# SCH_SrProj_v1_1.net
KiCad netlist of a schematic drawn in EasyEDA
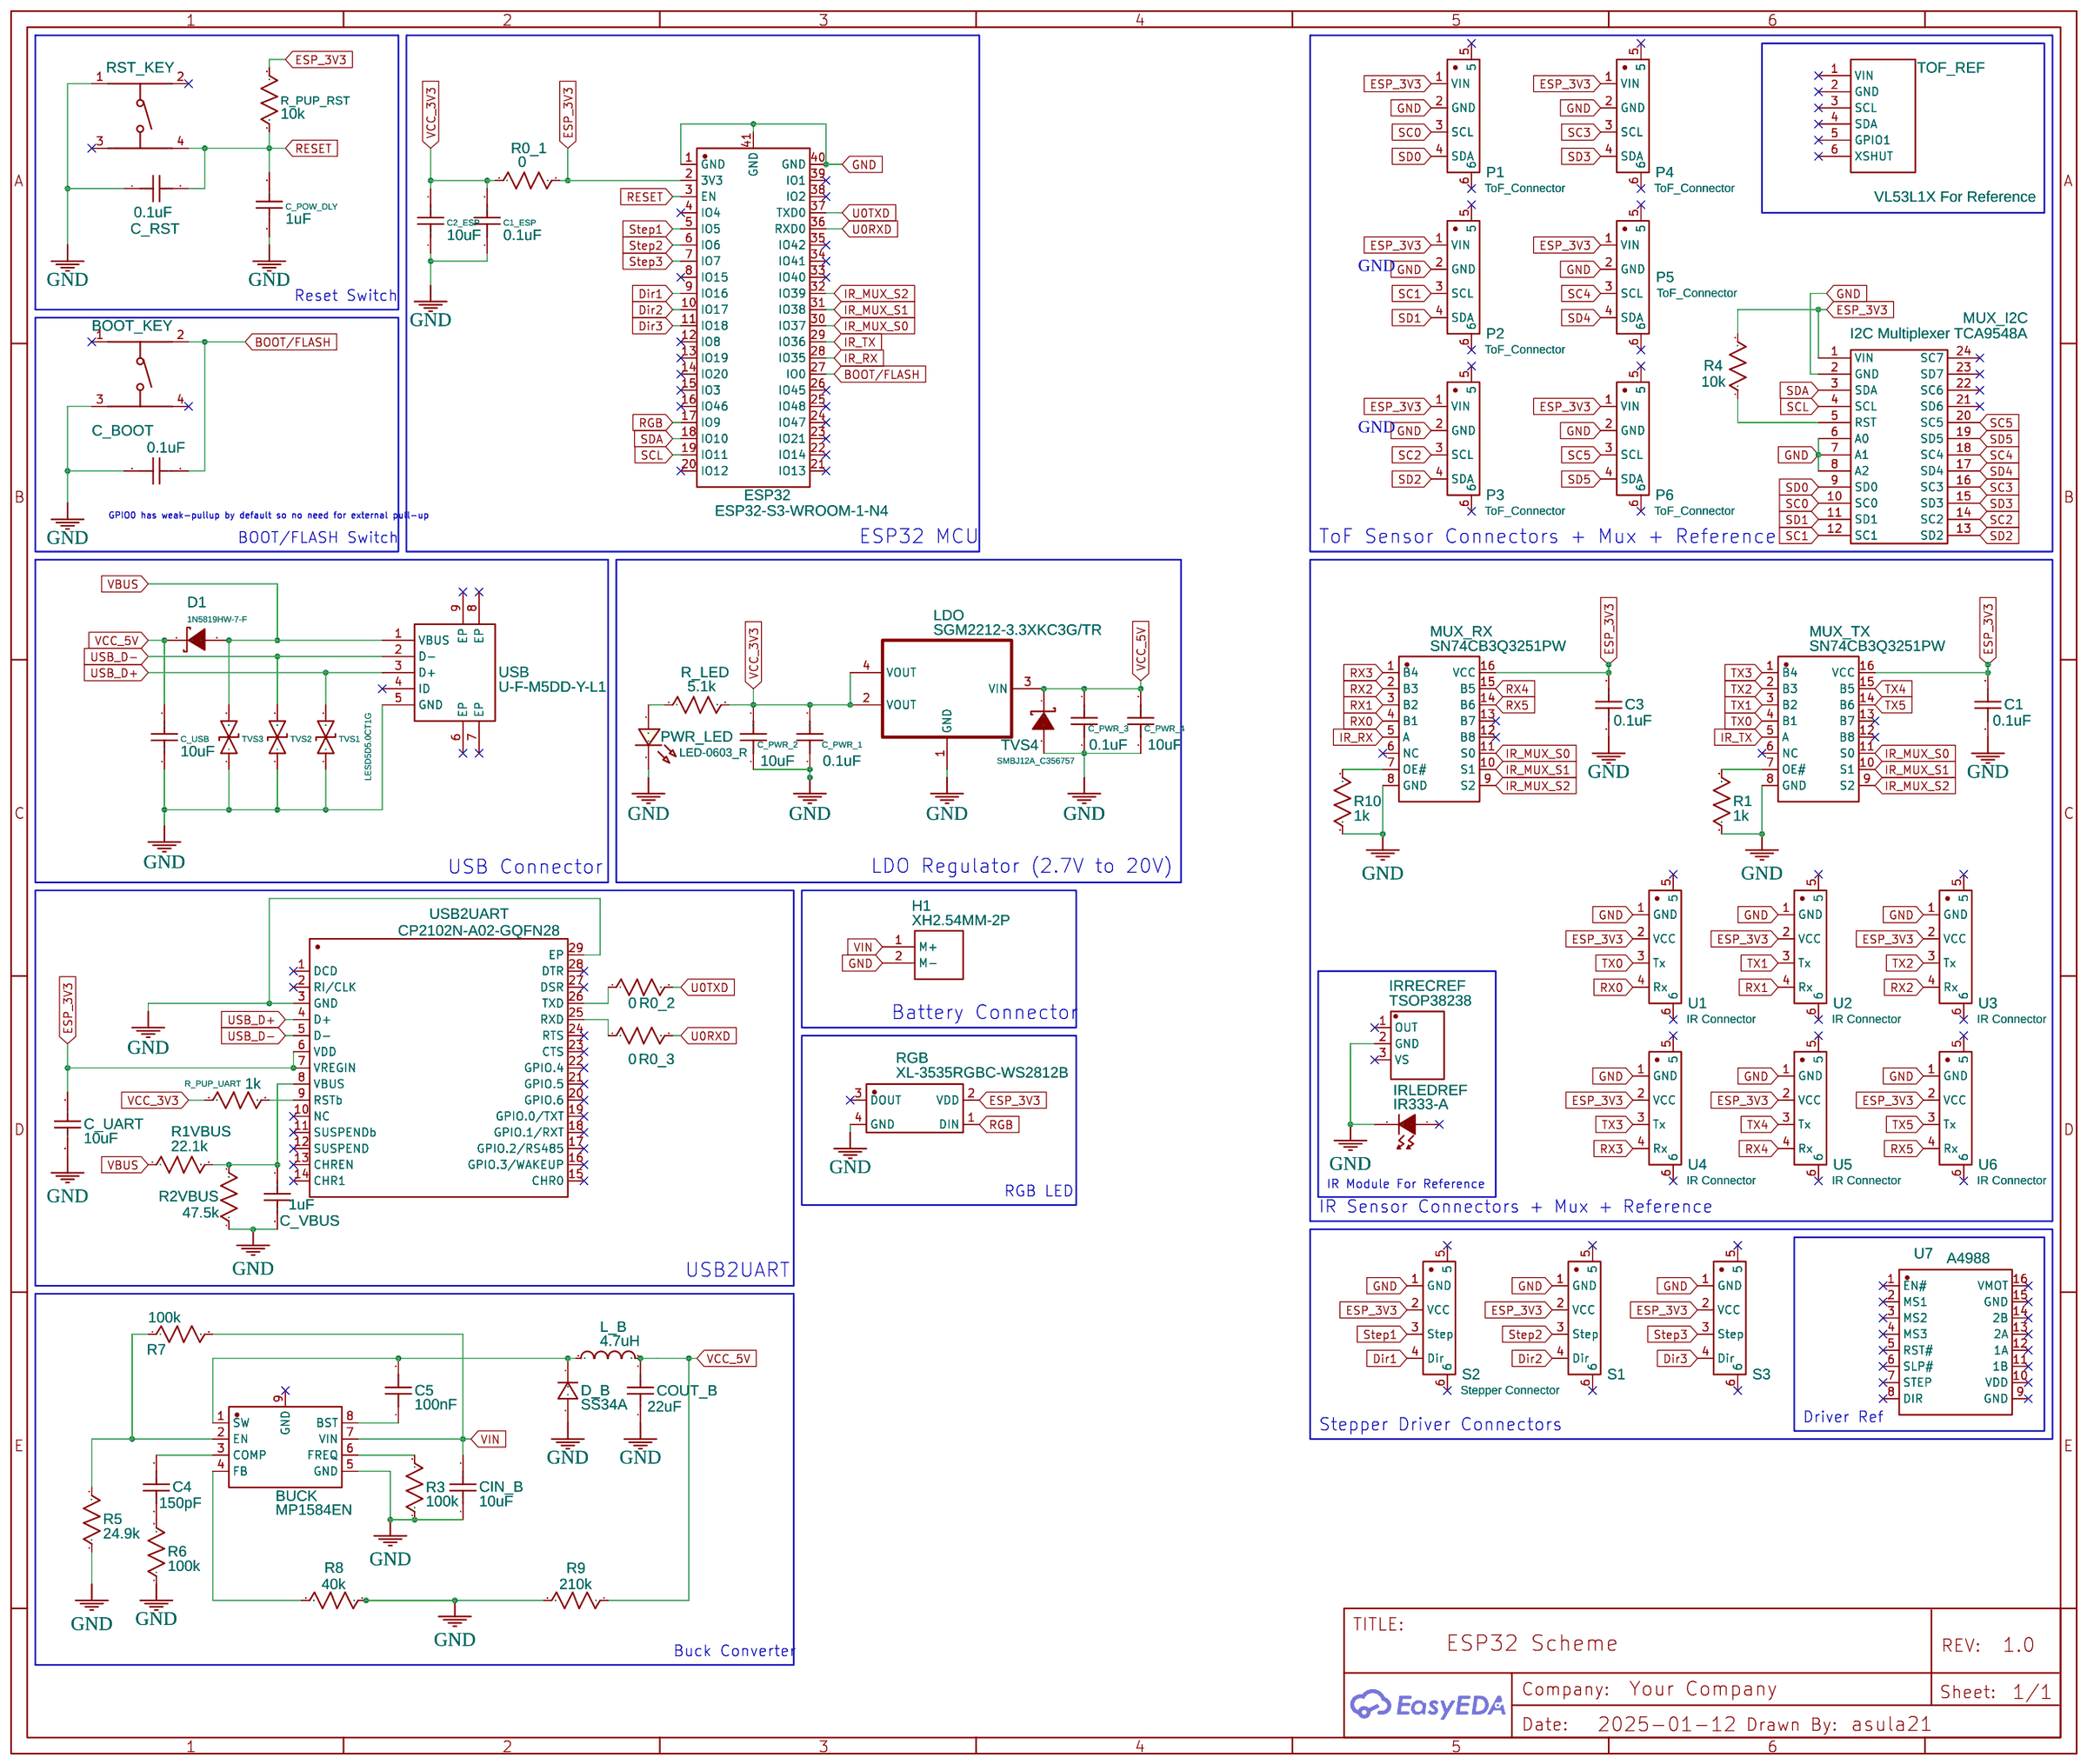
[diagram p0: schematic sheet]

(export (version "E")
  (design (tool "Eeschema 10.0.6"))
  (components
    (comp (ref "BOOT_KEY")
      (value "RSTBTN")
      (fields (field (name "Manufacturer Part") "BUTTON1"))
      (libsource (lib "") (part "BUTTON1_1"))
    )
    (comp (ref "BUCK") (value "MP1584EN") (libsource (lib "") (part "MP1584EN")))
    (comp (ref "C1") (value "0.1uF") (libsource (lib "") (part "C_0603_US_5")))
    (comp (ref "C1_ESP") (value "0.1uF") (libsource (lib "") (part "C_0603_US_10")))
    (comp (ref "C2_ESP") (value "10uF") (libsource (lib "") (part "C_0603_US_2")))
    (comp (ref "C3") (value "0.1uF") (libsource (lib "") (part "C_0603_US_5")))
    (comp (ref "C4") (value "150pF") (libsource (lib "") (part "C_0603_US_5")))
    (comp (ref "C5") (value "100nF") (libsource (lib "") (part "C_0603_US_5")))
    (comp (ref "CIN_B") (value "10uF") (libsource (lib "") (part "C_0603_US_7")))
    (comp (ref "COUT_B") (value "22uF") (libsource (lib "") (part "C_0603_US_9")))
    (comp (ref "C_BOOT") (value "0.1uF") (libsource (lib "") (part "C_0603_US_6")))
    (comp (ref "C_POW_DLY") (value "1uF") (libsource (lib "") (part "C_0603_US_8")))
    (comp (ref "C_PWR_1") (value "0.1uF") (libsource (lib "") (part "C_0603_US_1")))
    (comp (ref "C_PWR_2") (value "10uF") (libsource (lib "") (part "C_0603_US_1")))
    (comp (ref "C_PWR_3") (value "0.1uF") (libsource (lib "") (part "C_0603_US_1")))
    (comp (ref "C_PWR_4") (value "10uF") (libsource (lib "") (part "C_0603_US_1")))
    (comp (ref "C_RST") (value "0.1uF") (libsource (lib "") (part "C_0603_US_3")))
    (comp (ref "C_UART") (value "10uF") (libsource (lib "") (part "C_0603_US")))
    (comp (ref "C_USB") (value "10uF") (libsource (lib "") (part "C_0603_US_11")))
    (comp (ref "C_VBUS") (value "1uF") (libsource (lib "") (part "C_0603_US_4")))
    (comp (ref "D1")
      (value "1N5819HW-7-F")
      (fields (field (name "Manufacturer") "DIODES(美台)"))
      (libsource (lib "") (part "1N5819HW-7-F"))
    )
    (comp (ref "D_B")
      (value "SS34A")
      (fields (field (name "Manufacturer") "YANGJIE(扬杰)"))
      (libsource (lib "") (part "SS34A"))
    )
    (comp (ref "ESP32")
      (value "ESP32-S3-WROOM-1-N4")
      (fields (field (name "Manufacturer") "ESPRESSIF(乐鑫)"))
      (libsource (lib "") (part "ESP32-S3-WROOM-1-N4"))
    )
    (comp (ref "H1")
      (value "XH2.54MM-2P")
      (fields (field (name "Manufacturer Part") "Header P2 PH2.0 TUANLE"))
      (libsource (lib "") (part "PH2.0-2P"))
    )
    (comp (ref "IRLEDREF")
      (value "IR333-A")
      (fields (field (name "Manufacturer") "EVERLIGHT(亿光)"))
      (libsource (lib "") (part "IR333-A"))
    )
    (comp (ref "IRRECREF")
      (value "TSOP38238")
      (fields (field (name "Manufacturer") "VISHAY(威世)"))
      (libsource (lib "") (part "TSOP38238"))
    )
    (comp (ref "LDO") (value "SGM2212-3.3XKC3G/TR") (libsource (lib "") (part "SGM2212-3.3XKC3G/TR")))
    (comp (ref "L_B") (value "4.7uH") (libsource (lib "") (part "L0603_US")))
    (comp (ref "MUX_I2C")
      (value "I2C Multiplexer TCA9548A")
      (fields (field (name "Manufacturer Part") "IDSN-TCA9548A") (field (name "Manufacturer") "IDSN"))
      (libsource (lib "") (part "TCA9548A I2C MULTIPLEXER 8 CHANEL"))
    )
    (comp (ref "MUX_RX")
      (value "SN74CB3Q3251PW")
      (fields (field (name "Manufacturer") "TI(德州仪器)"))
      (libsource (lib "") (part "SN74CB3Q3251PW_1"))
    )
    (comp (ref "MUX_TX")
      (value "SN74CB3Q3251PW")
      (fields (field (name "Manufacturer") "TI(德州仪器)"))
      (libsource (lib "") (part "SN74CB3Q3251PW"))
    )
    (comp (ref "P1")
      (value "ToF_Connector")
      (fields (field (name "Manufacturer Part") "XH2.54MM-LI-4P"))
      (libsource (lib "") (part "XH2.54MM-LI-4P_1"))
    )
    (comp (ref "P2")
      (value "ToF_Connector")
      (fields (field (name "Manufacturer Part") "XH2.54MM-LI-4P"))
      (libsource (lib "") (part "XH2.54MM-LI-4P_1"))
    )
    (comp (ref "P3")
      (value "ToF_Connector")
      (fields (field (name "Manufacturer Part") "XH2.54MM-LI-4P"))
      (libsource (lib "") (part "XH2.54MM-LI-4P_1"))
    )
    (comp (ref "P4")
      (value "ToF_Connector")
      (fields (field (name "Manufacturer Part") "XH2.54MM-LI-4P"))
      (libsource (lib "") (part "XH2.54MM-LI-4P_1"))
    )
    (comp (ref "P5")
      (value "ToF_Connector")
      (fields (field (name "Manufacturer Part") "XH2.54MM-LI-4P"))
      (libsource (lib "") (part "XH2.54MM-LI-4P_1"))
    )
    (comp (ref "P6")
      (value "ToF_Connector")
      (fields (field (name "Manufacturer Part") "XH2.54MM-LI-4P"))
      (libsource (lib "") (part "XH2.54MM-LI-4P_1"))
    )
    (comp (ref "PWR_LED")
      (value "LED-0603_R")
      (fields
        (field (name "Manufacturer Part") "19-217/R6C-AL1M2VY/3T")
        (field (name "Manufacturer") "EVERLIGHT(台湾亿光)")
      )
      (libsource (lib "") (part "LED-0603_R"))
    )
    (comp (ref "R0_1") (value "0") (libsource (lib "") (part "R_0603_US_3")))
    (comp (ref "R0_2") (value "0") (libsource (lib "") (part "R_0603_US_3")))
    (comp (ref "R0_3") (value "0") (libsource (lib "") (part "R_0603_US_3")))
    (comp (ref "R1") (value "1k") (libsource (lib "") (part "R_0603_US")))
    (comp (ref "R1VBUS") (value "22.1k") (libsource (lib "") (part "R_0603_US_7")))
    (comp (ref "R2VBUS") (value "47.5k") (libsource (lib "") (part "R_0603_US_8")))
    (comp (ref "R3") (value "100k") (libsource (lib "") (part "R_0603_US")))
    (comp (ref "R4") (value "10k") (libsource (lib "") (part "R_0603_US")))
    (comp (ref "R5") (value "24.9k") (libsource (lib "") (part "R_0603_US")))
    (comp (ref "R6") (value "100k") (libsource (lib "") (part "R_0603_US")))
    (comp (ref "R7") (value "100k") (libsource (lib "") (part "R_0603_US_4")))
    (comp (ref "R8") (value "40k") (libsource (lib "") (part "R_0603_US_2")))
    (comp (ref "R9") (value "210k") (libsource (lib "") (part "R_0603_US_2")))
    (comp (ref "R10") (value "1k") (libsource (lib "") (part "R_0603_US")))
    (comp (ref "RGB")
      (value "XL-3535RGBC-WS2812B")
      (fields (field (name "Manufacturer") "XINGLIGHT(成兴光)"))
      (libsource (lib "") (part "XL-3535RGBC-WS2812B"))
    )
    (comp (ref "RST_KEY")
      (value "RSTBTN")
      (fields (field (name "Manufacturer Part") "BUTTON1"))
      (libsource (lib "") (part "BUTTON1"))
    )
    (comp (ref "R_LED") (value "5.1k") (libsource (lib "") (part "R_0603_US_1")))
    (comp (ref "R_PUP_RST") (value "10k") (libsource (lib "") (part "R_0603_US_6")))
    (comp (ref "R_PUP_UART") (value "1k") (libsource (lib "") (part "R_0603_US_5")))
    (comp (ref "S1")
      (value "Stepper Connector")
      (fields (field (name "Manufacturer Part") "XH2.54MM-LI-4P"))
      (libsource (lib "") (part "XH2.54MM-LI-4P_2"))
    )
    (comp (ref "S2")
      (value "Stepper Connector")
      (fields (field (name "Manufacturer Part") "XH2.54MM-LI-4P"))
      (libsource (lib "") (part "XH2.54MM-LI-4P_2"))
    )
    (comp (ref "S3")
      (value "Stepper Connector")
      (fields (field (name "Manufacturer Part") "XH2.54MM-LI-4P"))
      (libsource (lib "") (part "XH2.54MM-LI-4P_2"))
    )
    (comp (ref "TOF_REF")
      (value "VL53L1X For Reference")
      (fields (field (name "Manufacturer Part") "VL53L0X Time-of-Flight Distance Sensor VL53L0X"))
      (libsource (lib "") (part "VL53L1X_BREAKOUT"))
    )
    (comp (ref "TVS1")
      (value "LESD5D5.0CT1G")
      (fields (field (name "Manufacturer") "LRC(乐山无线电)"))
      (libsource (lib "") (part "LESD5D5.0CT1G"))
    )
    (comp (ref "TVS2")
      (value "LESD5D5.0CT1G")
      (fields (field (name "Manufacturer") "LRC(乐山无线电)"))
      (libsource (lib "") (part "LESD5D5.0CT1G"))
    )
    (comp (ref "TVS3")
      (value "LESD5D5.0CT1G")
      (fields (field (name "Manufacturer") "LRC(乐山无线电)"))
      (libsource (lib "") (part "LESD5D5.0CT1G"))
    )
    (comp (ref "TVS4")
      (value "SMBJ12A_C356757")
      (fields (field (name "Manufacturer Part") "SMBJ12A") (field (name "Manufacturer") "JJW(捷捷微)"))
      (libsource (lib "") (part "SMBJ12A_C356757"))
    )
    (comp (ref "U1")
      (value "IR Connector")
      (fields (field (name "Manufacturer Part") "XH2.54MM-LI-4P"))
      (libsource (lib "") (part "XH2.54MM-LI-4P"))
    )
    (comp (ref "U2")
      (value "IR Connector")
      (fields (field (name "Manufacturer Part") "XH2.54MM-LI-4P"))
      (libsource (lib "") (part "XH2.54MM-LI-4P"))
    )
    (comp (ref "U3")
      (value "IR Connector")
      (fields (field (name "Manufacturer Part") "XH2.54MM-LI-4P"))
      (libsource (lib "") (part "XH2.54MM-LI-4P"))
    )
    (comp (ref "U4")
      (value "IR Connector")
      (fields (field (name "Manufacturer Part") "XH2.54MM-LI-4P"))
      (libsource (lib "") (part "XH2.54MM-LI-4P"))
    )
    (comp (ref "U5")
      (value "IR Connector")
      (fields (field (name "Manufacturer Part") "XH2.54MM-LI-4P"))
      (libsource (lib "") (part "XH2.54MM-LI-4P"))
    )
    (comp (ref "U6")
      (value "IR Connector")
      (fields (field (name "Manufacturer Part") "XH2.54MM-LI-4P"))
      (libsource (lib "") (part "XH2.54MM-LI-4P"))
    )
    (comp (ref "U7") (value "A4988") (libsource (lib "") (part "A4988")))
    (comp (ref "USB")
      (value "U-F-M5DD-Y-L1")
      (fields (field (name "Manufacturer") "韩国韩荣"))
      (libsource (lib "") (part "U-F-M5DD-Y-L1"))
    )
    (comp (ref "USB2UART")
      (value "CP2102N-A02-GQFN28")
      (fields (field (name "Manufacturer") "SKYWORKS/SILICON LABS(芯科)"))
      (libsource (lib "") (part "CP2102N-A02-GQFN28"))
    )
  )
  (nets
    (net (code "1") (name "BOOT{slash}FLASH") (class "Default")
      (node (ref "BOOT_KEY") (pin "2") (pinfunction "2_2") (pintype "unspecified"))
      (node (ref "C_BOOT") (pin "2") (pinfunction "2_2") (pintype "unspecified"))
      (node (ref "ESP32") (pin "27") (pinfunction "IO0_27") (pintype "unspecified"))
    )
    (net (code "2") (name "Dir1") (class "Default")
      (node (ref "ESP32") (pin "9") (pinfunction "IO16_9") (pintype "unspecified"))
      (node (ref "S2") (pin "4") (pinfunction "Dir_4") (pintype "unspecified"))
    )
    (net (code "3") (name "Dir2") (class "Default")
      (node (ref "ESP32") (pin "10") (pinfunction "IO17_10") (pintype "unspecified"))
      (node (ref "S1") (pin "4") (pinfunction "Dir_4") (pintype "unspecified"))
    )
    (net (code "4") (name "Dir3") (class "Default")
      (node (ref "ESP32") (pin "11") (pinfunction "IO18_11") (pintype "unspecified"))
      (node (ref "S3") (pin "4") (pinfunction "Dir_4") (pintype "unspecified"))
    )
    (net (code "5") (name "ESP_3V3") (class "Default")
      (node (ref "C1") (pin "2") (pinfunction "2_2") (pintype "unspecified"))
      (node (ref "C3") (pin "2") (pinfunction "2_2") (pintype "unspecified"))
      (node (ref "C_UART") (pin "2") (pinfunction "2_2") (pintype "unspecified"))
      (node (ref "ESP32") (pin "2") (pinfunction "3V3_2") (pintype "unspecified"))
      (node (ref "MUX_I2C") (pin "1") (pinfunction "VIN_1") (pintype "unspecified"))
      (node (ref "MUX_RX") (pin "16") (pinfunction "VCC_16") (pintype "unspecified"))
      (node (ref "MUX_TX") (pin "16") (pinfunction "VCC_16") (pintype "unspecified"))
      (node (ref "P1") (pin "1") (pinfunction "VIN_1") (pintype "unspecified"))
      (node (ref "P2") (pin "1") (pinfunction "VIN_1") (pintype "unspecified"))
      (node (ref "P3") (pin "1") (pinfunction "VIN_1") (pintype "unspecified"))
      (node (ref "P4") (pin "1") (pinfunction "VIN_1") (pintype "unspecified"))
      (node (ref "P5") (pin "1") (pinfunction "VIN_1") (pintype "unspecified"))
      (node (ref "P6") (pin "1") (pinfunction "VIN_1") (pintype "unspecified"))
      (node (ref "R0_1") (pin "2") (pinfunction "2_2") (pintype "unspecified"))
      (node (ref "R4") (pin "2") (pinfunction "2_2") (pintype "unspecified"))
      (node (ref "RGB") (pin "2") (pinfunction "VDD_2") (pintype "unspecified"))
      (node (ref "R_PUP_RST") (pin "2") (pinfunction "2_2") (pintype "unspecified"))
      (node (ref "S1") (pin "2") (pinfunction "VCC_2") (pintype "unspecified"))
      (node (ref "S2") (pin "2") (pinfunction "VCC_2") (pintype "unspecified"))
      (node (ref "S3") (pin "2") (pinfunction "VCC_2") (pintype "unspecified"))
      (node (ref "U1") (pin "2") (pinfunction "VCC_2") (pintype "unspecified"))
      (node (ref "U2") (pin "2") (pinfunction "VCC_2") (pintype "unspecified"))
      (node (ref "U3") (pin "2") (pinfunction "VCC_2") (pintype "unspecified"))
      (node (ref "U4") (pin "2") (pinfunction "VCC_2") (pintype "unspecified"))
      (node (ref "U5") (pin "2") (pinfunction "VCC_2") (pintype "unspecified"))
      (node (ref "U6") (pin "2") (pinfunction "VCC_2") (pintype "unspecified"))
      (node (ref "USB2UART") (pin "6") (pinfunction "VDD_6") (pintype "unspecified"))
      (node (ref "USB2UART") (pin "7") (pinfunction "VREGIN_7") (pintype "unspecified"))
    )
    (net (code "6") (name "GND") (class "Default")
      (node (ref "BOOT_KEY") (pin "3") (pinfunction "3_3") (pintype "unspecified"))
      (node (ref "BUCK") (pin "5") (pinfunction "GND_5") (pintype "unspecified"))
      (node (ref "C1") (pin "1") (pinfunction "1_1") (pintype "unspecified"))
      (node (ref "C1_ESP") (pin "1") (pinfunction "1_1") (pintype "unspecified"))
      (node (ref "C2_ESP") (pin "1") (pinfunction "1_1") (pintype "unspecified"))
      (node (ref "C3") (pin "1") (pinfunction "1_1") (pintype "unspecified"))
      (node (ref "CIN_B") (pin "1") (pinfunction "1_1") (pintype "unspecified"))
      (node (ref "COUT_B") (pin "1") (pinfunction "1_1") (pintype "unspecified"))
      (node (ref "C_BOOT") (pin "1") (pinfunction "1_1") (pintype "unspecified"))
      (node (ref "C_POW_DLY") (pin "1") (pinfunction "1_1") (pintype "unspecified"))
      (node (ref "C_PWR_1") (pin "1") (pinfunction "1_1") (pintype "unspecified"))
      (node (ref "C_PWR_2") (pin "1") (pinfunction "1_1") (pintype "unspecified"))
      (node (ref "C_PWR_3") (pin "1") (pinfunction "1_1") (pintype "unspecified"))
      (node (ref "C_PWR_4") (pin "1") (pinfunction "1_1") (pintype "unspecified"))
      (node (ref "C_RST") (pin "1") (pinfunction "1_1") (pintype "unspecified"))
      (node (ref "C_UART") (pin "1") (pinfunction "1_1") (pintype "unspecified"))
      (node (ref "C_USB") (pin "1") (pinfunction "1_1") (pintype "unspecified"))
      (node (ref "C_VBUS") (pin "2") (pinfunction "2_2") (pintype "unspecified"))
      (node (ref "D_B") (pin "2") (pinfunction "A_2") (pintype "unspecified"))
      (node (ref "ESP32") (pin "1") (pinfunction "GND_1") (pintype "unspecified"))
      (node (ref "ESP32") (pin "40") (pinfunction "GND_40") (pintype "unspecified"))
      (node (ref "ESP32") (pin "41") (pinfunction "GND_41") (pintype "unspecified"))
      (node (ref "H1") (pin "2") (pinfunction "M-_2") (pintype "unspecified"))
      (node (ref "IRLEDREF") (pin "2") (pinfunction "C_2") (pintype "input"))
      (node (ref "IRRECREF") (pin "2") (pinfunction "GND_2") (pintype "unspecified"))
      (node (ref "LDO") (pin "1") (pinfunction "GND_1") (pintype "unspecified"))
      (node (ref "MUX_I2C") (pin "2") (pinfunction "GND_2") (pintype "unspecified"))
      (node (ref "MUX_I2C") (pin "6") (pinfunction "A0_6") (pintype "unspecified"))
      (node (ref "MUX_I2C") (pin "7") (pinfunction "A1_7") (pintype "unspecified"))
      (node (ref "MUX_I2C") (pin "8") (pinfunction "A2_8") (pintype "unspecified"))
      (node (ref "MUX_RX") (pin "8") (pinfunction "GND_8") (pintype "unspecified"))
      (node (ref "MUX_TX") (pin "8") (pinfunction "GND_8") (pintype "unspecified"))
      (node (ref "P1") (pin "2") (pinfunction "GND_2") (pintype "unspecified"))
      (node (ref "P2") (pin "2") (pinfunction "GND_2") (pintype "unspecified"))
      (node (ref "P3") (pin "2") (pinfunction "GND_2") (pintype "unspecified"))
      (node (ref "P4") (pin "2") (pinfunction "GND_2") (pintype "unspecified"))
      (node (ref "P5") (pin "2") (pinfunction "GND_2") (pintype "unspecified"))
      (node (ref "P6") (pin "2") (pinfunction "GND_2") (pintype "unspecified"))
      (node (ref "PWR_LED") (pin "2") (pinfunction "2_2") (pintype "unspecified"))
      (node (ref "R1") (pin "1") (pinfunction "1_1") (pintype "unspecified"))
      (node (ref "R10") (pin "1") (pinfunction "1_1") (pintype "unspecified"))
      (node (ref "R2VBUS") (pin "1") (pinfunction "1_1") (pintype "unspecified"))
      (node (ref "R3") (pin "1") (pinfunction "1_1") (pintype "unspecified"))
      (node (ref "R5") (pin "1") (pinfunction "1_1") (pintype "unspecified"))
      (node (ref "R6") (pin "1") (pinfunction "1_1") (pintype "unspecified"))
      (node (ref "R8") (pin "1") (pinfunction "1_1") (pintype "unspecified"))
      (node (ref "R9") (pin "2") (pinfunction "2_2") (pintype "unspecified"))
      (node (ref "RGB") (pin "4") (pinfunction "GND_4") (pintype "unspecified"))
      (node (ref "RST_KEY") (pin "1") (pinfunction "1_1") (pintype "unspecified"))
      (node (ref "S1") (pin "1") (pinfunction "GND_1") (pintype "unspecified"))
      (node (ref "S2") (pin "1") (pinfunction "GND_1") (pintype "unspecified"))
      (node (ref "S3") (pin "1") (pinfunction "GND_1") (pintype "unspecified"))
      (node (ref "TVS1") (pin "1") (pinfunction "1_1") (pintype "unspecified"))
      (node (ref "TVS2") (pin "1") (pinfunction "1_1") (pintype "unspecified"))
      (node (ref "TVS3") (pin "1") (pinfunction "1_1") (pintype "unspecified"))
      (node (ref "TVS4") (pin "2") (pinfunction "A_2") (pintype "unspecified"))
      (node (ref "U1") (pin "1") (pinfunction "GND_1") (pintype "unspecified"))
      (node (ref "U2") (pin "1") (pinfunction "GND_1") (pintype "unspecified"))
      (node (ref "U3") (pin "1") (pinfunction "GND_1") (pintype "unspecified"))
      (node (ref "U4") (pin "1") (pinfunction "GND_1") (pintype "unspecified"))
      (node (ref "U5") (pin "1") (pinfunction "GND_1") (pintype "unspecified"))
      (node (ref "U6") (pin "1") (pinfunction "GND_1") (pintype "unspecified"))
      (node (ref "USB") (pin "5") (pinfunction "GND_5") (pintype "unspecified"))
      (node (ref "USB2UART") (pin "29") (pinfunction "EP_29") (pintype "unspecified"))
      (node (ref "USB2UART") (pin "3") (pinfunction "GND_3") (pintype "unspecified"))
    )
    (net (code "7") (name "IR_MUX_S0") (class "Default")
      (node (ref "ESP32") (pin "30") (pinfunction "IO37_30") (pintype "unspecified"))
      (node (ref "MUX_RX") (pin "11") (pinfunction "S0_11") (pintype "unspecified"))
      (node (ref "MUX_TX") (pin "11") (pinfunction "S0_11") (pintype "unspecified"))
    )
    (net (code "8") (name "IR_MUX_S1") (class "Default")
      (node (ref "ESP32") (pin "31") (pinfunction "IO38_31") (pintype "unspecified"))
      (node (ref "MUX_RX") (pin "10") (pinfunction "S1_10") (pintype "unspecified"))
      (node (ref "MUX_TX") (pin "10") (pinfunction "S1_10") (pintype "unspecified"))
    )
    (net (code "9") (name "IR_MUX_S2") (class "Default")
      (node (ref "ESP32") (pin "32") (pinfunction "IO39_32") (pintype "unspecified"))
      (node (ref "MUX_RX") (pin "9") (pinfunction "S2_9") (pintype "unspecified"))
      (node (ref "MUX_TX") (pin "9") (pinfunction "S2_9") (pintype "unspecified"))
    )
    (net (code "10") (name "IR_RX") (class "Default")
      (node (ref "ESP32") (pin "28") (pinfunction "IO35_28") (pintype "unspecified"))
      (node (ref "MUX_RX") (pin "5") (pinfunction "A_5") (pintype "unspecified"))
    )
    (net (code "11") (name "IR_TX") (class "Default")
      (node (ref "ESP32") (pin "29") (pinfunction "IO36_29") (pintype "unspecified"))
      (node (ref "MUX_TX") (pin "5") (pinfunction "A_5") (pintype "unspecified"))
    )
    (net (code "12") (name "Net-(BUCK-BST)") (class "Default")
      (node (ref "BUCK") (pin "8") (pinfunction "BST_8") (pintype "unspecified"))
      (node (ref "C5") (pin "1") (pinfunction "1_1") (pintype "unspecified"))
    )
    (net (code "13") (name "Net-(BUCK-COMP)") (class "Default")
      (node (ref "BUCK") (pin "3") (pinfunction "COMP_3") (pintype "unspecified"))
      (node (ref "C4") (pin "2") (pinfunction "2_2") (pintype "unspecified"))
    )
    (net (code "14") (name "Net-(BUCK-EN)") (class "Default")
      (node (ref "BUCK") (pin "2") (pinfunction "EN_2") (pintype "unspecified"))
      (node (ref "R5") (pin "2") (pinfunction "2_2") (pintype "unspecified"))
      (node (ref "R7") (pin "1") (pinfunction "1_1") (pintype "unspecified"))
    )
    (net (code "15") (name "Net-(BUCK-FB)") (class "Default")
      (node (ref "BUCK") (pin "4") (pinfunction "FB_4") (pintype "unspecified"))
      (node (ref "R8") (pin "2") (pinfunction "2_2") (pintype "unspecified"))
    )
    (net (code "16") (name "Net-(BUCK-FREQ)") (class "Default")
      (node (ref "BUCK") (pin "6") (pinfunction "FREQ_6") (pintype "unspecified"))
      (node (ref "R3") (pin "2") (pinfunction "2_2") (pintype "unspecified"))
    )
    (net (code "17") (name "Net-(BUCK-SW)") (class "Default")
      (node (ref "BUCK") (pin "1") (pinfunction "SW_1") (pintype "unspecified"))
      (node (ref "C5") (pin "2") (pinfunction "2_2") (pintype "unspecified"))
      (node (ref "D_B") (pin "1") (pinfunction "C_1") (pintype "unspecified"))
      (node (ref "L_B") (pin "1") (pinfunction "1_1") (pintype "unspecified"))
    )
    (net (code "18") (name "Net-(C4-Pad1)") (class "Default")
      (node (ref "C4") (pin "1") (pinfunction "1_1") (pintype "unspecified"))
      (node (ref "R6") (pin "2") (pinfunction "2_2") (pintype "unspecified"))
    )
    (net (code "19") (name "Net-(MUX_I2C-RST)") (class "Default")
      (node (ref "MUX_I2C") (pin "5") (pinfunction "RST_5") (pintype "unspecified"))
      (node (ref "R4") (pin "1") (pinfunction "1_1") (pintype "unspecified"))
    )
    (net (code "20") (name "Net-(MUX_RX-OE#)") (class "Default")
      (node (ref "MUX_RX") (pin "7") (pinfunction "OE#_7") (pintype "unspecified"))
      (node (ref "R10") (pin "2") (pinfunction "2_2") (pintype "unspecified"))
    )
    (net (code "21") (name "Net-(MUX_TX-OE#)") (class "Default")
      (node (ref "MUX_TX") (pin "7") (pinfunction "OE#_7") (pintype "unspecified"))
      (node (ref "R1") (pin "2") (pinfunction "2_2") (pintype "unspecified"))
    )
    (net (code "22") (name "Net-(PWR_LED-Pad1)") (class "Default")
      (node (ref "PWR_LED") (pin "1") (pinfunction "1_1") (pintype "unspecified"))
      (node (ref "R_LED") (pin "1") (pinfunction "1_1") (pintype "unspecified"))
    )
    (net (code "23") (name "Net-(USB2UART-RSTb)") (class "Default")
      (node (ref "R_PUP_UART") (pin "1") (pinfunction "1_1") (pintype "unspecified"))
      (node (ref "USB2UART") (pin "9") (pinfunction "RSTb_9") (pintype "unspecified"))
    )
    (net (code "24") (name "Net-(USB2UART-RXD)") (class "Default")
      (node (ref "R0_3") (pin "1") (pinfunction "1_1") (pintype "unspecified"))
      (node (ref "USB2UART") (pin "25") (pinfunction "RXD_25") (pintype "unspecified"))
    )
    (net (code "25") (name "Net-(USB2UART-TXD)") (class "Default")
      (node (ref "R0_2") (pin "1") (pinfunction "1_1") (pintype "unspecified"))
      (node (ref "USB2UART") (pin "26") (pinfunction "TXD_26") (pintype "unspecified"))
    )
    (net (code "26") (name "Net-(USB2UART-VBUS)") (class "Default")
      (node (ref "C_VBUS") (pin "1") (pinfunction "1_1") (pintype "unspecified"))
      (node (ref "R1VBUS") (pin "2") (pinfunction "2_2") (pintype "unspecified"))
      (node (ref "R2VBUS") (pin "2") (pinfunction "2_2") (pintype "unspecified"))
      (node (ref "USB2UART") (pin "8") (pinfunction "VBUS_8") (pintype "unspecified"))
    )
    (net (code "27") (name "RESET") (class "Default")
      (node (ref "C_POW_DLY") (pin "2") (pinfunction "2_2") (pintype "unspecified"))
      (node (ref "C_RST") (pin "2") (pinfunction "2_2") (pintype "unspecified"))
      (node (ref "ESP32") (pin "3") (pinfunction "EN_3") (pintype "unspecified"))
      (node (ref "RST_KEY") (pin "4") (pinfunction "4_4") (pintype "unspecified"))
      (node (ref "R_PUP_RST") (pin "1") (pinfunction "1_1") (pintype "unspecified"))
    )
    (net (code "28") (name "RGB") (class "Default")
      (node (ref "ESP32") (pin "17") (pinfunction "IO9_17") (pintype "unspecified"))
      (node (ref "RGB") (pin "1") (pinfunction "DIN_1") (pintype "unspecified"))
    )
    (net (code "29") (name "RX0") (class "Default")
      (node (ref "MUX_RX") (pin "4") (pinfunction "B1_4") (pintype "unspecified"))
      (node (ref "U1") (pin "4") (pinfunction "Rx_4") (pintype "unspecified"))
    )
    (net (code "30") (name "RX1") (class "Default")
      (node (ref "MUX_RX") (pin "3") (pinfunction "B2_3") (pintype "unspecified"))
      (node (ref "U2") (pin "4") (pinfunction "Rx_4") (pintype "unspecified"))
    )
    (net (code "31") (name "RX2") (class "Default")
      (node (ref "MUX_RX") (pin "2") (pinfunction "B3_2") (pintype "unspecified"))
      (node (ref "U3") (pin "4") (pinfunction "Rx_4") (pintype "unspecified"))
    )
    (net (code "32") (name "RX3") (class "Default")
      (node (ref "MUX_RX") (pin "1") (pinfunction "B4_1") (pintype "unspecified"))
      (node (ref "U4") (pin "4") (pinfunction "Rx_4") (pintype "unspecified"))
    )
    (net (code "33") (name "RX4") (class "Default")
      (node (ref "MUX_RX") (pin "15") (pinfunction "B5_15") (pintype "unspecified"))
      (node (ref "U5") (pin "4") (pinfunction "Rx_4") (pintype "unspecified"))
    )
    (net (code "34") (name "RX5") (class "Default")
      (node (ref "MUX_RX") (pin "14") (pinfunction "B6_14") (pintype "unspecified"))
      (node (ref "U6") (pin "4") (pinfunction "Rx_4") (pintype "unspecified"))
    )
    (net (code "35") (name "SC0") (class "Default")
      (node (ref "MUX_I2C") (pin "10") (pinfunction "SC0_10") (pintype "unspecified"))
      (node (ref "P1") (pin "3") (pinfunction "SCL_3") (pintype "unspecified"))
    )
    (net (code "36") (name "SC1") (class "Default")
      (node (ref "MUX_I2C") (pin "12") (pinfunction "SC1_12") (pintype "unspecified"))
      (node (ref "P2") (pin "3") (pinfunction "SCL_3") (pintype "unspecified"))
    )
    (net (code "37") (name "SC2") (class "Default")
      (node (ref "MUX_I2C") (pin "14") (pinfunction "SC2_14") (pintype "unspecified"))
      (node (ref "P3") (pin "3") (pinfunction "SCL_3") (pintype "unspecified"))
    )
    (net (code "38") (name "SC3") (class "Default")
      (node (ref "MUX_I2C") (pin "16") (pinfunction "SC3_16") (pintype "unspecified"))
      (node (ref "P4") (pin "3") (pinfunction "SCL_3") (pintype "unspecified"))
    )
    (net (code "39") (name "SC4") (class "Default")
      (node (ref "MUX_I2C") (pin "18") (pinfunction "SC4_18") (pintype "unspecified"))
      (node (ref "P5") (pin "3") (pinfunction "SCL_3") (pintype "unspecified"))
    )
    (net (code "40") (name "SC5") (class "Default")
      (node (ref "MUX_I2C") (pin "20") (pinfunction "SC5_20") (pintype "unspecified"))
      (node (ref "P6") (pin "3") (pinfunction "SCL_3") (pintype "unspecified"))
    )
    (net (code "41") (name "SCL") (class "Default")
      (node (ref "ESP32") (pin "19") (pinfunction "IO11_19") (pintype "unspecified"))
      (node (ref "MUX_I2C") (pin "4") (pinfunction "SCL_4") (pintype "unspecified"))
    )
    (net (code "42") (name "SD0") (class "Default")
      (node (ref "MUX_I2C") (pin "9") (pinfunction "SD0_9") (pintype "unspecified"))
      (node (ref "P1") (pin "4") (pinfunction "SDA_4") (pintype "unspecified"))
    )
    (net (code "43") (name "SD1") (class "Default")
      (node (ref "MUX_I2C") (pin "11") (pinfunction "SD1_11") (pintype "unspecified"))
      (node (ref "P2") (pin "4") (pinfunction "SDA_4") (pintype "unspecified"))
    )
    (net (code "44") (name "SD2") (class "Default")
      (node (ref "MUX_I2C") (pin "13") (pinfunction "SD2_13") (pintype "unspecified"))
      (node (ref "P3") (pin "4") (pinfunction "SDA_4") (pintype "unspecified"))
    )
    (net (code "45") (name "SD3") (class "Default")
      (node (ref "MUX_I2C") (pin "15") (pinfunction "SD3_15") (pintype "unspecified"))
      (node (ref "P4") (pin "4") (pinfunction "SDA_4") (pintype "unspecified"))
    )
    (net (code "46") (name "SD4") (class "Default")
      (node (ref "MUX_I2C") (pin "17") (pinfunction "SD4_17") (pintype "unspecified"))
      (node (ref "P5") (pin "4") (pinfunction "SDA_4") (pintype "unspecified"))
    )
    (net (code "47") (name "SD5") (class "Default")
      (node (ref "MUX_I2C") (pin "19") (pinfunction "SD5_19") (pintype "unspecified"))
      (node (ref "P6") (pin "4") (pinfunction "SDA_4") (pintype "unspecified"))
    )
    (net (code "48") (name "SDA") (class "Default")
      (node (ref "ESP32") (pin "18") (pinfunction "IO10_18") (pintype "unspecified"))
      (node (ref "MUX_I2C") (pin "3") (pinfunction "SDA_3") (pintype "unspecified"))
    )
    (net (code "49") (name "Step1") (class "Default")
      (node (ref "ESP32") (pin "5") (pinfunction "IO5_5") (pintype "unspecified"))
      (node (ref "S2") (pin "3") (pinfunction "Step_3") (pintype "unspecified"))
    )
    (net (code "50") (name "Step2") (class "Default")
      (node (ref "ESP32") (pin "6") (pinfunction "IO6_6") (pintype "unspecified"))
      (node (ref "S1") (pin "3") (pinfunction "Step_3") (pintype "unspecified"))
    )
    (net (code "51") (name "Step3") (class "Default")
      (node (ref "ESP32") (pin "7") (pinfunction "IO7_7") (pintype "unspecified"))
      (node (ref "S3") (pin "3") (pinfunction "Step_3") (pintype "unspecified"))
    )
    (net (code "52") (name "TX0") (class "Default")
      (node (ref "MUX_TX") (pin "4") (pinfunction "B1_4") (pintype "unspecified"))
      (node (ref "U1") (pin "3") (pinfunction "Tx_3") (pintype "unspecified"))
    )
    (net (code "53") (name "TX1") (class "Default")
      (node (ref "MUX_TX") (pin "3") (pinfunction "B2_3") (pintype "unspecified"))
      (node (ref "U2") (pin "3") (pinfunction "Tx_3") (pintype "unspecified"))
    )
    (net (code "54") (name "TX2") (class "Default")
      (node (ref "MUX_TX") (pin "2") (pinfunction "B3_2") (pintype "unspecified"))
      (node (ref "U3") (pin "3") (pinfunction "Tx_3") (pintype "unspecified"))
    )
    (net (code "55") (name "TX3") (class "Default")
      (node (ref "MUX_TX") (pin "1") (pinfunction "B4_1") (pintype "unspecified"))
      (node (ref "U4") (pin "3") (pinfunction "Tx_3") (pintype "unspecified"))
    )
    (net (code "56") (name "TX4") (class "Default")
      (node (ref "MUX_TX") (pin "15") (pinfunction "B5_15") (pintype "unspecified"))
      (node (ref "U5") (pin "3") (pinfunction "Tx_3") (pintype "unspecified"))
    )
    (net (code "57") (name "TX5") (class "Default")
      (node (ref "MUX_TX") (pin "14") (pinfunction "B6_14") (pintype "unspecified"))
      (node (ref "U6") (pin "3") (pinfunction "Tx_3") (pintype "unspecified"))
    )
    (net (code "58") (name "U0RXD") (class "Default")
      (node (ref "ESP32") (pin "36") (pinfunction "RXD0_36") (pintype "unspecified"))
      (node (ref "R0_3") (pin "2") (pinfunction "2_2") (pintype "unspecified"))
    )
    (net (code "59") (name "U0TXD") (class "Default")
      (node (ref "ESP32") (pin "37") (pinfunction "TXD0_37") (pintype "unspecified"))
      (node (ref "R0_2") (pin "2") (pinfunction "2_2") (pintype "unspecified"))
    )
    (net (code "60") (name "USB_D+") (class "Default")
      (node (ref "TVS1") (pin "2") (pinfunction "2_2") (pintype "unspecified"))
      (node (ref "USB") (pin "3") (pinfunction "D+_3") (pintype "unspecified"))
      (node (ref "USB2UART") (pin "4") (pinfunction "D+_4") (pintype "unspecified"))
    )
    (net (code "61") (name "USB_D-") (class "Default")
      (node (ref "TVS2") (pin "2") (pinfunction "2_2") (pintype "unspecified"))
      (node (ref "USB") (pin "2") (pinfunction "D-_2") (pintype "unspecified"))
      (node (ref "USB2UART") (pin "5") (pinfunction "D-_5") (pintype "unspecified"))
    )
    (net (code "62") (name "VBUS") (class "Default")
      (node (ref "D1") (pin "2") (pinfunction "A_2") (pintype "unspecified"))
      (node (ref "R1VBUS") (pin "1") (pinfunction "1_1") (pintype "unspecified"))
      (node (ref "TVS3") (pin "2") (pinfunction "2_2") (pintype "unspecified"))
      (node (ref "USB") (pin "1") (pinfunction "VBUS_1") (pintype "unspecified"))
    )
    (net (code "63") (name "VCC_3V3") (class "Default")
      (node (ref "C1_ESP") (pin "2") (pinfunction "2_2") (pintype "unspecified"))
      (node (ref "C2_ESP") (pin "2") (pinfunction "2_2") (pintype "unspecified"))
      (node (ref "C_PWR_1") (pin "2") (pinfunction "2_2") (pintype "unspecified"))
      (node (ref "C_PWR_2") (pin "2") (pinfunction "2_2") (pintype "unspecified"))
      (node (ref "LDO") (pin "2") (pinfunction "VOUT_2") (pintype "unspecified"))
      (node (ref "LDO") (pin "4") (pinfunction "VOUT_4") (pintype "unspecified"))
      (node (ref "R0_1") (pin "1") (pinfunction "1_1") (pintype "unspecified"))
      (node (ref "R_LED") (pin "2") (pinfunction "2_2") (pintype "unspecified"))
      (node (ref "R_PUP_UART") (pin "2") (pinfunction "2_2") (pintype "unspecified"))
    )
    (net (code "64") (name "VCC_5V") (class "Default")
      (node (ref "COUT_B") (pin "2") (pinfunction "2_2") (pintype "unspecified"))
      (node (ref "C_PWR_3") (pin "2") (pinfunction "2_2") (pintype "unspecified"))
      (node (ref "C_PWR_4") (pin "2") (pinfunction "2_2") (pintype "unspecified"))
      (node (ref "C_USB") (pin "2") (pinfunction "2_2") (pintype "unspecified"))
      (node (ref "D1") (pin "1") (pinfunction "K_1") (pintype "unspecified"))
      (node (ref "LDO") (pin "3") (pinfunction "VIN_3") (pintype "unspecified"))
      (node (ref "L_B") (pin "2") (pinfunction "2_2") (pintype "unspecified"))
      (node (ref "R9") (pin "1") (pinfunction "1_1") (pintype "unspecified"))
      (node (ref "TVS4") (pin "1") (pinfunction "K_1") (pintype "unspecified"))
    )
    (net (code "65") (name "VIN") (class "Default")
      (node (ref "BUCK") (pin "7") (pinfunction "VIN_7") (pintype "unspecified"))
      (node (ref "CIN_B") (pin "2") (pinfunction "2_2") (pintype "unspecified"))
      (node (ref "H1") (pin "1") (pinfunction "M+_1") (pintype "unspecified"))
      (node (ref "R7") (pin "2") (pinfunction "2_2") (pintype "unspecified"))
    )
    (net (code "66") (name "unconnected-(BOOT_KEY-Pad1)") (class "Default")
      (node (ref "BOOT_KEY") (pin "1") (pinfunction "1_1") (pintype "unspecified+no_connect"))
    )
    (net (code "67") (name "unconnected-(BOOT_KEY-Pad4)") (class "Default")
      (node (ref "BOOT_KEY") (pin "4") (pinfunction "4_4") (pintype "unspecified+no_connect"))
    )
    (net (code "68") (name "unconnected-(BUCK-GND-Pad9)") (class "Default")
      (node (ref "BUCK") (pin "9") (pinfunction "GND_9") (pintype "unspecified+no_connect"))
    )
    (net (code "69") (name "unconnected-(ESP32-IO1-Pad39)") (class "Default")
      (node (ref "ESP32") (pin "39") (pinfunction "IO1_39") (pintype "unspecified+no_connect"))
    )
    (net (code "70") (name "unconnected-(ESP32-IO2-Pad38)") (class "Default")
      (node (ref "ESP32") (pin "38") (pinfunction "IO2_38") (pintype "unspecified+no_connect"))
    )
    (net (code "71") (name "unconnected-(ESP32-IO3-Pad15)") (class "Default")
      (node (ref "ESP32") (pin "15") (pinfunction "IO3_15") (pintype "unspecified+no_connect"))
    )
    (net (code "72") (name "unconnected-(ESP32-IO4-Pad4)") (class "Default")
      (node (ref "ESP32") (pin "4") (pinfunction "IO4_4") (pintype "unspecified+no_connect"))
    )
    (net (code "73") (name "unconnected-(ESP32-IO8-Pad12)") (class "Default")
      (node (ref "ESP32") (pin "12") (pinfunction "IO8_12") (pintype "unspecified+no_connect"))
    )
    (net (code "74") (name "unconnected-(ESP32-IO12-Pad20)") (class "Default")
      (node (ref "ESP32") (pin "20") (pinfunction "IO12_20") (pintype "unspecified+no_connect"))
    )
    (net (code "75") (name "unconnected-(ESP32-IO13-Pad21)") (class "Default")
      (node (ref "ESP32") (pin "21") (pinfunction "IO13_21") (pintype "unspecified+no_connect"))
    )
    (net (code "76") (name "unconnected-(ESP32-IO14-Pad22)") (class "Default")
      (node (ref "ESP32") (pin "22") (pinfunction "IO14_22") (pintype "unspecified+no_connect"))
    )
    (net (code "77") (name "unconnected-(ESP32-IO15-Pad8)") (class "Default")
      (node (ref "ESP32") (pin "8") (pinfunction "IO15_8") (pintype "unspecified+no_connect"))
    )
    (net (code "78") (name "unconnected-(ESP32-IO19-Pad13)") (class "Default")
      (node (ref "ESP32") (pin "13") (pinfunction "IO19_13") (pintype "unspecified+no_connect"))
    )
    (net (code "79") (name "unconnected-(ESP32-IO20-Pad14)") (class "Default")
      (node (ref "ESP32") (pin "14") (pinfunction "IO20_14") (pintype "unspecified+no_connect"))
    )
    (net (code "80") (name "unconnected-(ESP32-IO21-Pad23)") (class "Default")
      (node (ref "ESP32") (pin "23") (pinfunction "IO21_23") (pintype "unspecified+no_connect"))
    )
    (net (code "81") (name "unconnected-(ESP32-IO40-Pad33)") (class "Default")
      (node (ref "ESP32") (pin "33") (pinfunction "IO40_33") (pintype "unspecified+no_connect"))
    )
    (net (code "82") (name "unconnected-(ESP32-IO41-Pad34)") (class "Default")
      (node (ref "ESP32") (pin "34") (pinfunction "IO41_34") (pintype "unspecified+no_connect"))
    )
    (net (code "83") (name "unconnected-(ESP32-IO42-Pad35)") (class "Default")
      (node (ref "ESP32") (pin "35") (pinfunction "IO42_35") (pintype "unspecified+no_connect"))
    )
    (net (code "84") (name "unconnected-(ESP32-IO45-Pad26)") (class "Default")
      (node (ref "ESP32") (pin "26") (pinfunction "IO45_26") (pintype "unspecified+no_connect"))
    )
    (net (code "85") (name "unconnected-(ESP32-IO46-Pad16)") (class "Default")
      (node (ref "ESP32") (pin "16") (pinfunction "IO46_16") (pintype "unspecified+no_connect"))
    )
    (net (code "86") (name "unconnected-(ESP32-IO47-Pad24)") (class "Default")
      (node (ref "ESP32") (pin "24") (pinfunction "IO47_24") (pintype "unspecified+no_connect"))
    )
    (net (code "87") (name "unconnected-(ESP32-IO48-Pad25)") (class "Default")
      (node (ref "ESP32") (pin "25") (pinfunction "IO48_25") (pintype "unspecified+no_connect"))
    )
    (net (code "88") (name "unconnected-(IRLEDREF-A-Pad1)") (class "Default")
      (node (ref "IRLEDREF") (pin "1") (pinfunction "A_1") (pintype "input+no_connect"))
    )
    (net (code "89") (name "unconnected-(IRRECREF-OUT-Pad1)") (class "Default")
      (node (ref "IRRECREF") (pin "1") (pinfunction "OUT_1") (pintype "unspecified+no_connect"))
    )
    (net (code "90") (name "unconnected-(IRRECREF-VS-Pad3)") (class "Default")
      (node (ref "IRRECREF") (pin "3") (pinfunction "VS_3") (pintype "unspecified+no_connect"))
    )
    (net (code "91") (name "unconnected-(MUX_I2C-SC6-Pad22)") (class "Default")
      (node (ref "MUX_I2C") (pin "22") (pinfunction "SC6_22") (pintype "unspecified+no_connect"))
    )
    (net (code "92") (name "unconnected-(MUX_I2C-SC7-Pad24)") (class "Default")
      (node (ref "MUX_I2C") (pin "24") (pinfunction "SC7_24") (pintype "unspecified+no_connect"))
    )
    (net (code "93") (name "unconnected-(MUX_I2C-SD6-Pad21)") (class "Default")
      (node (ref "MUX_I2C") (pin "21") (pinfunction "SD6_21") (pintype "unspecified+no_connect"))
    )
    (net (code "94") (name "unconnected-(MUX_I2C-SD7-Pad23)") (class "Default")
      (node (ref "MUX_I2C") (pin "23") (pinfunction "SD7_23") (pintype "unspecified+no_connect"))
    )
    (net (code "95") (name "unconnected-(MUX_RX-B7-Pad13)") (class "Default")
      (node (ref "MUX_RX") (pin "13") (pinfunction "B7_13") (pintype "unspecified+no_connect"))
    )
    (net (code "96") (name "unconnected-(MUX_RX-B8-Pad12)") (class "Default")
      (node (ref "MUX_RX") (pin "12") (pinfunction "B8_12") (pintype "unspecified+no_connect"))
    )
    (net (code "97") (name "unconnected-(MUX_RX-NC-Pad6)") (class "Default")
      (node (ref "MUX_RX") (pin "6") (pinfunction "NC_6") (pintype "unspecified+no_connect"))
    )
    (net (code "98") (name "unconnected-(MUX_TX-B7-Pad13)") (class "Default")
      (node (ref "MUX_TX") (pin "13") (pinfunction "B7_13") (pintype "unspecified+no_connect"))
    )
    (net (code "99") (name "unconnected-(MUX_TX-B8-Pad12)") (class "Default")
      (node (ref "MUX_TX") (pin "12") (pinfunction "B8_12") (pintype "unspecified+no_connect"))
    )
    (net (code "100") (name "unconnected-(MUX_TX-NC-Pad6)") (class "Default")
      (node (ref "MUX_TX") (pin "6") (pinfunction "NC_6") (pintype "unspecified+no_connect"))
    )
    (net (code "101") (name "unconnected-(P1-Pad5)") (class "Default")
      (node (ref "P1") (pin "5") (pinfunction "5_5") (pintype "unspecified+no_connect"))
    )
    (net (code "102") (name "unconnected-(P1-Pad6)") (class "Default")
      (node (ref "P1") (pin "6") (pinfunction "6_6") (pintype "unspecified+no_connect"))
    )
    (net (code "103") (name "unconnected-(P2-Pad5)") (class "Default")
      (node (ref "P2") (pin "5") (pinfunction "5_5") (pintype "unspecified+no_connect"))
    )
    (net (code "104") (name "unconnected-(P2-Pad6)") (class "Default")
      (node (ref "P2") (pin "6") (pinfunction "6_6") (pintype "unspecified+no_connect"))
    )
    (net (code "105") (name "unconnected-(P3-Pad5)") (class "Default")
      (node (ref "P3") (pin "5") (pinfunction "5_5") (pintype "unspecified+no_connect"))
    )
    (net (code "106") (name "unconnected-(P3-Pad6)") (class "Default")
      (node (ref "P3") (pin "6") (pinfunction "6_6") (pintype "unspecified+no_connect"))
    )
    (net (code "107") (name "unconnected-(P4-Pad5)") (class "Default")
      (node (ref "P4") (pin "5") (pinfunction "5_5") (pintype "unspecified+no_connect"))
    )
    (net (code "108") (name "unconnected-(P4-Pad6)") (class "Default")
      (node (ref "P4") (pin "6") (pinfunction "6_6") (pintype "unspecified+no_connect"))
    )
    (net (code "109") (name "unconnected-(P5-Pad5)") (class "Default")
      (node (ref "P5") (pin "5") (pinfunction "5_5") (pintype "unspecified+no_connect"))
    )
    (net (code "110") (name "unconnected-(P5-Pad6)") (class "Default")
      (node (ref "P5") (pin "6") (pinfunction "6_6") (pintype "unspecified+no_connect"))
    )
    (net (code "111") (name "unconnected-(P6-Pad5)") (class "Default")
      (node (ref "P6") (pin "5") (pinfunction "5_5") (pintype "unspecified+no_connect"))
    )
    (net (code "112") (name "unconnected-(P6-Pad6)") (class "Default")
      (node (ref "P6") (pin "6") (pinfunction "6_6") (pintype "unspecified+no_connect"))
    )
    (net (code "113") (name "unconnected-(RGB-DOUT-Pad3)") (class "Default")
      (node (ref "RGB") (pin "3") (pinfunction "DOUT_3") (pintype "unspecified+no_connect"))
    )
    (net (code "114") (name "unconnected-(RST_KEY-Pad2)") (class "Default")
      (node (ref "RST_KEY") (pin "2") (pinfunction "2_2") (pintype "unspecified+no_connect"))
    )
    (net (code "115") (name "unconnected-(RST_KEY-Pad3)") (class "Default")
      (node (ref "RST_KEY") (pin "3") (pinfunction "3_3") (pintype "unspecified+no_connect"))
    )
    (net (code "116") (name "unconnected-(S1-Pad5)") (class "Default")
      (node (ref "S1") (pin "5") (pinfunction "5_5") (pintype "unspecified+no_connect"))
    )
    (net (code "117") (name "unconnected-(S1-Pad6)") (class "Default")
      (node (ref "S1") (pin "6") (pinfunction "6_6") (pintype "unspecified+no_connect"))
    )
    (net (code "118") (name "unconnected-(S2-Pad5)") (class "Default")
      (node (ref "S2") (pin "5") (pinfunction "5_5") (pintype "unspecified+no_connect"))
    )
    (net (code "119") (name "unconnected-(S2-Pad6)") (class "Default")
      (node (ref "S2") (pin "6") (pinfunction "6_6") (pintype "unspecified+no_connect"))
    )
    (net (code "120") (name "unconnected-(S3-Pad5)") (class "Default")
      (node (ref "S3") (pin "5") (pinfunction "5_5") (pintype "unspecified+no_connect"))
    )
    (net (code "121") (name "unconnected-(S3-Pad6)") (class "Default")
      (node (ref "S3") (pin "6") (pinfunction "6_6") (pintype "unspecified+no_connect"))
    )
    (net (code "122") (name "unconnected-(TOF_REF-GND-Pad2)") (class "Default")
      (node (ref "TOF_REF") (pin "2") (pinfunction "GND_2") (pintype "unspecified+no_connect"))
    )
    (net (code "123") (name "unconnected-(TOF_REF-GPIO1-Pad5)") (class "Default")
      (node (ref "TOF_REF") (pin "5") (pinfunction "GPIO1_5") (pintype "unspecified+no_connect"))
    )
    (net (code "124") (name "unconnected-(TOF_REF-SCL-Pad3)") (class "Default")
      (node (ref "TOF_REF") (pin "3") (pinfunction "SCL_3") (pintype "unspecified+no_connect"))
    )
    (net (code "125") (name "unconnected-(TOF_REF-SDA-Pad4)") (class "Default")
      (node (ref "TOF_REF") (pin "4") (pinfunction "SDA_4") (pintype "unspecified+no_connect"))
    )
    (net (code "126") (name "unconnected-(TOF_REF-VIN-Pad1)") (class "Default")
      (node (ref "TOF_REF") (pin "1") (pinfunction "VIN_1") (pintype "unspecified+no_connect"))
    )
    (net (code "127") (name "unconnected-(TOF_REF-XSHUT-Pad6)") (class "Default")
      (node (ref "TOF_REF") (pin "6") (pinfunction "XSHUT_6") (pintype "unspecified+no_connect"))
    )
    (net (code "128") (name "unconnected-(U1-Pad5)") (class "Default")
      (node (ref "U1") (pin "5") (pinfunction "5_5") (pintype "unspecified+no_connect"))
    )
    (net (code "129") (name "unconnected-(U1-Pad6)") (class "Default")
      (node (ref "U1") (pin "6") (pinfunction "6_6") (pintype "unspecified+no_connect"))
    )
    (net (code "130") (name "unconnected-(U2-Pad5)") (class "Default")
      (node (ref "U2") (pin "5") (pinfunction "5_5") (pintype "unspecified+no_connect"))
    )
    (net (code "131") (name "unconnected-(U2-Pad6)") (class "Default")
      (node (ref "U2") (pin "6") (pinfunction "6_6") (pintype "unspecified+no_connect"))
    )
    (net (code "132") (name "unconnected-(U3-Pad5)") (class "Default")
      (node (ref "U3") (pin "5") (pinfunction "5_5") (pintype "unspecified+no_connect"))
    )
    (net (code "133") (name "unconnected-(U3-Pad6)") (class "Default")
      (node (ref "U3") (pin "6") (pinfunction "6_6") (pintype "unspecified+no_connect"))
    )
    (net (code "134") (name "unconnected-(U4-Pad5)") (class "Default")
      (node (ref "U4") (pin "5") (pinfunction "5_5") (pintype "unspecified+no_connect"))
    )
    (net (code "135") (name "unconnected-(U4-Pad6)") (class "Default")
      (node (ref "U4") (pin "6") (pinfunction "6_6") (pintype "unspecified+no_connect"))
    )
    (net (code "136") (name "unconnected-(U5-Pad5)") (class "Default")
      (node (ref "U5") (pin "5") (pinfunction "5_5") (pintype "unspecified+no_connect"))
    )
    (net (code "137") (name "unconnected-(U5-Pad6)") (class "Default")
      (node (ref "U5") (pin "6") (pinfunction "6_6") (pintype "unspecified+no_connect"))
    )
    (net (code "138") (name "unconnected-(U6-Pad5)") (class "Default")
      (node (ref "U6") (pin "5") (pinfunction "5_5") (pintype "unspecified+no_connect"))
    )
    (net (code "139") (name "unconnected-(U6-Pad6)") (class "Default")
      (node (ref "U6") (pin "6") (pinfunction "6_6") (pintype "unspecified+no_connect"))
    )
    (net (code "140") (name "unconnected-(U7-1A-Pad12)") (class "Default")
      (node (ref "U7") (pin "12") (pinfunction "1A_12") (pintype "unspecified+no_connect"))
    )
    (net (code "141") (name "unconnected-(U7-1B-Pad11)") (class "Default")
      (node (ref "U7") (pin "11") (pinfunction "1B_11") (pintype "unspecified+no_connect"))
    )
    (net (code "142") (name "unconnected-(U7-2A-Pad13)") (class "Default")
      (node (ref "U7") (pin "13") (pinfunction "2A_13") (pintype "unspecified+no_connect"))
    )
    (net (code "143") (name "unconnected-(U7-2B-Pad14)") (class "Default")
      (node (ref "U7") (pin "14") (pinfunction "2B_14") (pintype "unspecified+no_connect"))
    )
    (net (code "144") (name "unconnected-(U7-DIR-Pad8)") (class "Default")
      (node (ref "U7") (pin "8") (pinfunction "DIR_8") (pintype "unspecified+no_connect"))
    )
    (net (code "145") (name "unconnected-(U7-EN#-Pad1)") (class "Default")
      (node (ref "U7") (pin "1") (pinfunction "EN#_1") (pintype "unspecified+no_connect"))
    )
    (net (code "146") (name "unconnected-(U7-GND-Pad9)") (class "Default")
      (node (ref "U7") (pin "9") (pinfunction "GND_9") (pintype "unspecified+no_connect"))
    )
    (net (code "147") (name "unconnected-(U7-GND-Pad15)") (class "Default")
      (node (ref "U7") (pin "15") (pinfunction "GND_15") (pintype "unspecified+no_connect"))
    )
    (net (code "148") (name "unconnected-(U7-MS1-Pad2)") (class "Default")
      (node (ref "U7") (pin "2") (pinfunction "MS1_2") (pintype "unspecified+no_connect"))
    )
    (net (code "149") (name "unconnected-(U7-MS2-Pad3)") (class "Default")
      (node (ref "U7") (pin "3") (pinfunction "MS2_3") (pintype "unspecified+no_connect"))
    )
    (net (code "150") (name "unconnected-(U7-MS3-Pad4)") (class "Default")
      (node (ref "U7") (pin "4") (pinfunction "MS3_4") (pintype "unspecified+no_connect"))
    )
    (net (code "151") (name "unconnected-(U7-RST#-Pad5)") (class "Default")
      (node (ref "U7") (pin "5") (pinfunction "RST#_5") (pintype "unspecified+no_connect"))
    )
    (net (code "152") (name "unconnected-(U7-SLP#-Pad6)") (class "Default")
      (node (ref "U7") (pin "6") (pinfunction "SLP#_6") (pintype "unspecified+no_connect"))
    )
    (net (code "153") (name "unconnected-(U7-STEP-Pad7)") (class "Default")
      (node (ref "U7") (pin "7") (pinfunction "STEP_7") (pintype "unspecified+no_connect"))
    )
    (net (code "154") (name "unconnected-(U7-VDD-Pad10)") (class "Default")
      (node (ref "U7") (pin "10") (pinfunction "VDD_10") (pintype "unspecified+no_connect"))
    )
    (net (code "155") (name "unconnected-(U7-VMOT-Pad16)") (class "Default")
      (node (ref "U7") (pin "16") (pinfunction "VMOT_16") (pintype "unspecified+no_connect"))
    )
    (net (code "156") (name "unconnected-(USB-EP-Pad6)") (class "Default")
      (node (ref "USB") (pin "6") (pinfunction "EP_6") (pintype "unspecified+no_connect"))
    )
    (net (code "157") (name "unconnected-(USB-EP-Pad7)") (class "Default")
      (node (ref "USB") (pin "7") (pinfunction "EP_7") (pintype "unspecified+no_connect"))
    )
    (net (code "158") (name "unconnected-(USB-EP-Pad8)") (class "Default")
      (node (ref "USB") (pin "8") (pinfunction "EP_8") (pintype "unspecified+no_connect"))
    )
    (net (code "159") (name "unconnected-(USB-EP-Pad9)") (class "Default")
      (node (ref "USB") (pin "9") (pinfunction "EP_9") (pintype "unspecified+no_connect"))
    )
    (net (code "160") (name "unconnected-(USB-ID-Pad4)") (class "Default")
      (node (ref "USB") (pin "4") (pinfunction "ID_4") (pintype "unspecified+no_connect"))
    )
    (net (code "161") (name "unconnected-(USB2UART-CHR0-Pad15)") (class "Default")
      (node (ref "USB2UART") (pin "15") (pinfunction "CHR0_15") (pintype "unspecified+no_connect"))
    )
    (net (code "162") (name "unconnected-(USB2UART-CHR1-Pad14)") (class "Default")
      (node (ref "USB2UART") (pin "14") (pinfunction "CHR1_14") (pintype "unspecified+no_connect"))
    )
    (net (code "163") (name "unconnected-(USB2UART-CHREN-Pad13)") (class "Default")
      (node (ref "USB2UART") (pin "13") (pinfunction "CHREN_13") (pintype "unspecified+no_connect"))
    )
    (net (code "164") (name "unconnected-(USB2UART-CTS-Pad23)") (class "Default")
      (node (ref "USB2UART") (pin "23") (pinfunction "CTS_23") (pintype "unspecified+no_connect"))
    )
    (net (code "165") (name "unconnected-(USB2UART-DCD-Pad1)") (class "Default")
      (node (ref "USB2UART") (pin "1") (pinfunction "DCD_1") (pintype "unspecified+no_connect"))
    )
    (net (code "166") (name "unconnected-(USB2UART-DSR-Pad27)") (class "Default")
      (node (ref "USB2UART") (pin "27") (pinfunction "DSR_27") (pintype "unspecified+no_connect"))
    )
    (net (code "167") (name "unconnected-(USB2UART-DTR-Pad28)") (class "Default")
      (node (ref "USB2UART") (pin "28") (pinfunction "DTR_28") (pintype "unspecified+no_connect"))
    )
    (net (code "168") (name "unconnected-(USB2UART-GPIO.0{slash}TXT-Pad19)") (class "Default")
      (node (ref "USB2UART") (pin "19") (pinfunction "GPIO.0/TXT_19") (pintype "unspecified+no_connect"))
    )
    (net (code "169") (name "unconnected-(USB2UART-GPIO.1{slash}RXT-Pad18)") (class "Default")
      (node (ref "USB2UART") (pin "18") (pinfunction "GPIO.1/RXT_18") (pintype "unspecified+no_connect"))
    )
    (net (code "170") (name "unconnected-(USB2UART-GPIO.2{slash}RS485-Pad17)") (class "Default")
      (node (ref "USB2UART") (pin "17") (pinfunction "GPIO.2/RS485_17") (pintype "unspecified+no_connect"))
    )
    (net (code "171") (name "unconnected-(USB2UART-GPIO.3{slash}WAKEUP-Pad16)") (class "Default")
      (node (ref "USB2UART") (pin "16") (pinfunction "GPIO.3/WAKEUP_16") (pintype "unspecified+no_connect"))
    )
    (net (code "172") (name "unconnected-(USB2UART-GPIO.4-Pad22)") (class "Default")
      (node (ref "USB2UART") (pin "22") (pinfunction "GPIO.4_22") (pintype "unspecified+no_connect"))
    )
    (net (code "173") (name "unconnected-(USB2UART-GPIO.5-Pad21)") (class "Default")
      (node (ref "USB2UART") (pin "21") (pinfunction "GPIO.5_21") (pintype "unspecified+no_connect"))
    )
    (net (code "174") (name "unconnected-(USB2UART-GPIO.6-Pad20)") (class "Default")
      (node (ref "USB2UART") (pin "20") (pinfunction "GPIO.6_20") (pintype "unspecified+no_connect"))
    )
    (net (code "175") (name "unconnected-(USB2UART-NC-Pad10)") (class "Default")
      (node (ref "USB2UART") (pin "10") (pinfunction "NC_10") (pintype "unspecified+no_connect"))
    )
    (net (code "176") (name "unconnected-(USB2UART-RI{slash}CLK-Pad2)") (class "Default")
      (node (ref "USB2UART") (pin "2") (pinfunction "RI/CLK_2") (pintype "unspecified+no_connect"))
    )
    (net (code "177") (name "unconnected-(USB2UART-RTS-Pad24)") (class "Default")
      (node (ref "USB2UART") (pin "24") (pinfunction "RTS_24") (pintype "unspecified+no_connect"))
    )
    (net (code "178") (name "unconnected-(USB2UART-SUSPEND-Pad12)") (class "Default")
      (node (ref "USB2UART") (pin "12") (pinfunction "SUSPEND_12") (pintype "unspecified+no_connect"))
    )
    (net (code "179") (name "unconnected-(USB2UART-SUSPENDb-Pad11)") (class "Default")
      (node (ref "USB2UART") (pin "11") (pinfunction "SUSPENDb_11") (pintype "unspecified+no_connect"))
    )
  )
)
